# arduinoISP.net
KiCad netlist of a schematic drawn in EAGLE
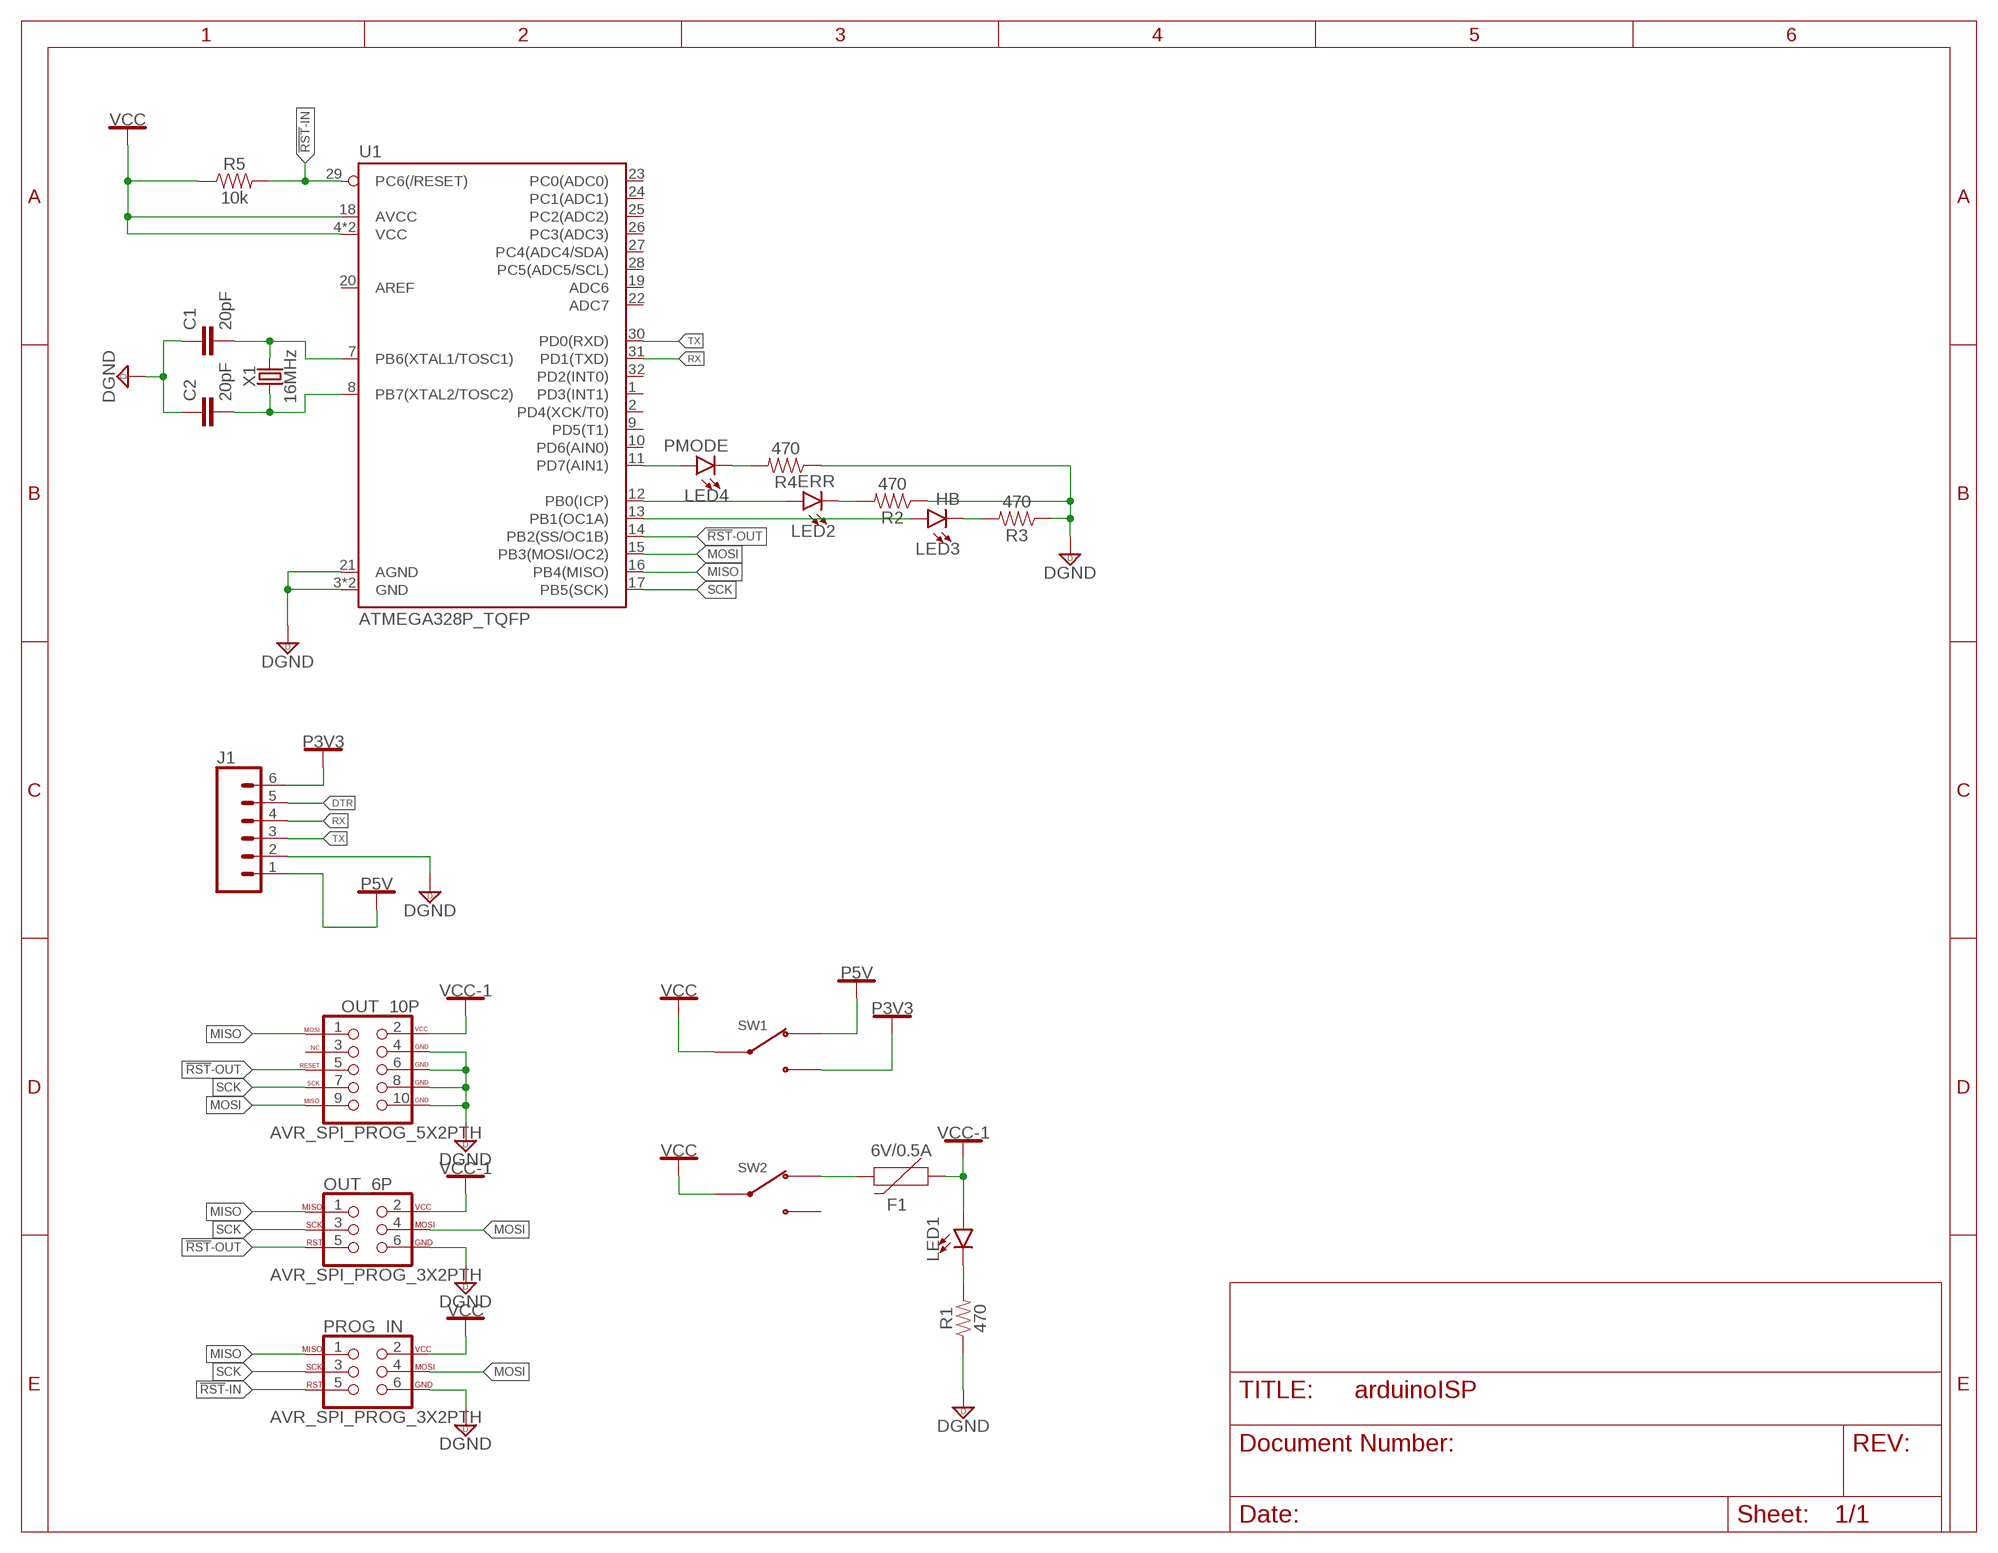
[diagram p0: schematic, sheet 1]

(export (version "E")
  (design (tool "Eeschema 10.0.6"))
  (components
    (comp (ref "C1")
      (value "20pF")
      (footprint "eagle-import:0603")
      (libsource (lib "eagle-import") (part "CAPACITOR_SMT_0603"))
    )
    (comp (ref "C2")
      (value "20pF")
      (footprint "eagle-import:0603")
      (libsource (lib "eagle-import") (part "CAPACITOR_SMT_0603"))
    )
    (comp (ref "F1")
      (value "6V/0.5A")
      (footprint "eagle-import:1206")
      (libsource (lib "eagle-import") (part "PPTC_HALF-AMP"))
    )
    (comp (ref "J1")
      (value "CONN_06NO_SILK_NO_POP")
      (footprint "eagle-import:1X06_NO_SILK")
      (libsource (lib "eagle-import") (part "CONN_06NO_SILK_NO_POP"))
    )
    (comp (ref "LED1")
      (value "LED3MM")
      (footprint "eagle-import:LED_3MM")
      (libsource (lib "eagle-import") (part "LED3MM"))
    )
    (comp (ref "LED2")
      (value "ERR")
      (footprint "eagle-import:LED_3MM")
      (libsource (lib "eagle-import") (part "LED3MM"))
    )
    (comp (ref "LED3")
      (value "HB")
      (footprint "eagle-import:LED_3MM")
      (libsource (lib "eagle-import") (part "LED3MM"))
    )
    (comp (ref "LED4")
      (value "PMODE")
      (footprint "eagle-import:LED_3MM")
      (libsource (lib "eagle-import") (part "LED3MM"))
    )
    (comp (ref "OUT_6P")
      (value "AVR_SPI_PROG_3X2PTH")
      (footprint "eagle-import:2X3")
      (libsource (lib "eagle-import") (part "AVR_SPI_PROG_3X2PTH"))
    )
    (comp (ref "OUT_10P")
      (value "AVR_SPI_PROG_5X2PTH")
      (footprint "eagle-import:2X5")
      (libsource (lib "eagle-import") (part "AVR_SPI_PROG_5X2PTH"))
    )
    (comp (ref "PROG_IN")
      (value "AVR_SPI_PROG_3X2PTH")
      (footprint "eagle-import:2X3")
      (libsource (lib "eagle-import") (part "AVR_SPI_PROG_3X2PTH"))
    )
    (comp (ref "R1")
      (value "470")
      (footprint "eagle-import:0603")
      (libsource (lib "eagle-import") (part "RESISTOR_SMT_0603"))
    )
    (comp (ref "R2")
      (value "470")
      (footprint "eagle-import:0603")
      (libsource (lib "eagle-import") (part "RESISTOR_SMT_0603"))
    )
    (comp (ref "R3")
      (value "470")
      (footprint "eagle-import:0603")
      (libsource (lib "eagle-import") (part "RESISTOR_SMT_0603"))
    )
    (comp (ref "R4")
      (value "470")
      (footprint "eagle-import:0603")
      (libsource (lib "eagle-import") (part "RESISTOR_SMT_0603"))
    )
    (comp (ref "R5")
      (value "10k")
      (footprint "eagle-import:0603")
      (libsource (lib "eagle-import") (part "RESISTOR_SMT_0603"))
    )
    (comp (ref "SW1")
      (value "SW-SPDT_SS-12D02-VG4")
      (footprint "eagle-import:SW_SS-12D10L5_FP")
      (libsource (lib "eagle-import") (part "SW-SPDT_SS-12D02-VG4"))
    )
    (comp (ref "SW2")
      (value "SW-SPDT_SS-12D02-VG4")
      (footprint "eagle-import:SW_SS-12D10L5_FP")
      (libsource (lib "eagle-import") (part "SW-SPDT_SS-12D02-VG4"))
    )
    (comp (ref "U1")
      (value "ATMEGA328P_TQFP")
      (footprint "eagle-import:TQFP32-08")
      (libsource (lib "eagle-import") (part "ATMEGA328P_TQFP"))
    )
    (comp (ref "X1")
      (value "16MHz")
      (footprint "eagle-import:HC49US")
      (libsource (lib "eagle-import") (part "CRYSTAL-16MHZPTH-HC49US"))
    )
  )
  (nets
    (net (code "1") (name "/~{RST}-IN") (class "Default")
      (node (ref "PROG_IN") (pin "5") (pinfunction "5_5") (pintype "passive"))
      (node (ref "R5") (pin "2") (pinfunction "2_2") (pintype "passive"))
      (node (ref "U1") (pin "29") (pinfunction "PC6(/RESET)_29") (pintype "bidirectional"))
    )
    (net (code "2") (name "/~{RST}-OUT") (class "Default")
      (node (ref "OUT_10P") (pin "5") (pinfunction "RESET_5") (pintype "passive"))
      (node (ref "OUT_6P") (pin "5") (pinfunction "5_5") (pintype "passive"))
      (node (ref "U1") (pin "14") (pinfunction "PB2(SS/OC1B)_14") (pintype "bidirectional"))
    )
    (net (code "3") (name "DGND") (class "Default")
      (node (ref "C1") (pin "1") (pinfunction "1_1") (pintype "passive"))
      (node (ref "C2") (pin "1") (pinfunction "1_1") (pintype "passive"))
      (node (ref "J1") (pin "2") (pinfunction "2_2") (pintype "passive"))
      (node (ref "OUT_10P") (pin "10") (pinfunction "GND_10") (pintype "power_in"))
      (node (ref "OUT_10P") (pin "4") (pinfunction "GND_4") (pintype "power_in"))
      (node (ref "OUT_10P") (pin "6") (pinfunction "GND_6") (pintype "power_in"))
      (node (ref "OUT_10P") (pin "8") (pinfunction "GND_8") (pintype "power_in"))
      (node (ref "OUT_6P") (pin "6") (pinfunction "6_6") (pintype "passive"))
      (node (ref "PROG_IN") (pin "6") (pinfunction "6_6") (pintype "passive"))
      (node (ref "R1") (pin "1") (pinfunction "1_1") (pintype "passive"))
      (node (ref "R2") (pin "1") (pinfunction "1_1") (pintype "passive"))
      (node (ref "R3") (pin "1") (pinfunction "1_1") (pintype "passive"))
      (node (ref "R4") (pin "1") (pinfunction "1_1") (pintype "passive"))
      (node (ref "U1") (pin "21") (pinfunction "AGND_21") (pintype "bidirectional"))
      (node (ref "U1") (pin "3") (pinfunction "GND_3") (pintype "bidirectional"))
      (node (ref "U1") (pin "5") (pinfunction "GND_5") (pintype "bidirectional"))
    )
    (net (code "4") (name "DTR") (class "Default")
      (node (ref "J1") (pin "5") (pinfunction "5_5") (pintype "passive"))
    )
    (net (code "5") (name "MISO") (class "Default")
      (node (ref "OUT_10P") (pin "1") (pinfunction "MOSI_1") (pintype "passive"))
      (node (ref "OUT_6P") (pin "1") (pinfunction "1_1") (pintype "passive"))
      (node (ref "PROG_IN") (pin "1") (pinfunction "1_1") (pintype "passive"))
      (node (ref "U1") (pin "16") (pinfunction "PB4(MISO)_16") (pintype "bidirectional"))
    )
    (net (code "6") (name "MOSI") (class "Default")
      (node (ref "OUT_10P") (pin "9") (pinfunction "MISO_9") (pintype "passive"))
      (node (ref "OUT_6P") (pin "4") (pinfunction "4_4") (pintype "passive"))
      (node (ref "PROG_IN") (pin "4") (pinfunction "4_4") (pintype "passive"))
      (node (ref "U1") (pin "15") (pinfunction "PB3(MOSI/OC2)_15") (pintype "bidirectional"))
    )
    (net (code "7") (name "Net-(LED1-C)") (class "Default")
      (node (ref "LED1") (pin "K") (pinfunction "C_K") (pintype "passive"))
      (node (ref "R1") (pin "2") (pinfunction "2_2") (pintype "passive"))
    )
    (net (code "8") (name "Net-(LED2-C)") (class "Default")
      (node (ref "LED2") (pin "K") (pinfunction "C_K") (pintype "passive"))
      (node (ref "R2") (pin "2") (pinfunction "2_2") (pintype "passive"))
    )
    (net (code "9") (name "Net-(LED3-C)") (class "Default")
      (node (ref "LED3") (pin "K") (pinfunction "C_K") (pintype "passive"))
      (node (ref "R3") (pin "2") (pinfunction "2_2") (pintype "passive"))
    )
    (net (code "10") (name "Net-(LED4-C)") (class "Default")
      (node (ref "LED4") (pin "K") (pinfunction "C_K") (pintype "passive"))
      (node (ref "R4") (pin "2") (pinfunction "2_2") (pintype "passive"))
    )
    (net (code "11") (name "Net-(SW2-A)") (class "Default")
      (node (ref "F1") (pin "2") (pinfunction "2_2") (pintype "bidirectional"))
      (node (ref "SW2") (pin "P$1") (pinfunction "A_P$1") (pintype "bidirectional"))
    )
    (net (code "12") (name "Net-(U1-PB0(ICP))") (class "Default")
      (node (ref "LED2") (pin "A") (pinfunction "A_A") (pintype "passive"))
      (node (ref "U1") (pin "12") (pinfunction "PB0(ICP)_12") (pintype "bidirectional"))
    )
    (net (code "13") (name "Net-(U1-PB1(OC1A))") (class "Default")
      (node (ref "LED3") (pin "A") (pinfunction "A_A") (pintype "passive"))
      (node (ref "U1") (pin "13") (pinfunction "PB1(OC1A)_13") (pintype "bidirectional"))
    )
    (net (code "14") (name "Net-(U1-PB6(XTAL1{slash}TOSC1))") (class "Default")
      (node (ref "C1") (pin "2") (pinfunction "2_2") (pintype "passive"))
      (node (ref "U1") (pin "7") (pinfunction "PB6(XTAL1/TOSC1)_7") (pintype "bidirectional"))
      (node (ref "X1") (pin "2") (pinfunction "2_2") (pintype "passive"))
    )
    (net (code "15") (name "Net-(U1-PB7(XTAL2{slash}TOSC2))") (class "Default")
      (node (ref "C2") (pin "2") (pinfunction "2_2") (pintype "passive"))
      (node (ref "U1") (pin "8") (pinfunction "PB7(XTAL2/TOSC2)_8") (pintype "bidirectional"))
      (node (ref "X1") (pin "1") (pinfunction "1_1") (pintype "passive"))
    )
    (net (code "16") (name "Net-(U1-PD7(AIN1))") (class "Default")
      (node (ref "LED4") (pin "A") (pinfunction "A_A") (pintype "passive"))
      (node (ref "U1") (pin "11") (pinfunction "PD7(AIN1)_11") (pintype "bidirectional"))
    )
    (net (code "17") (name "P3V3") (class "Default")
      (node (ref "J1") (pin "6") (pinfunction "6_6") (pintype "passive"))
      (node (ref "SW1") (pin "P$3") (pinfunction "B_P$3") (pintype "bidirectional"))
    )
    (net (code "18") (name "P5V") (class "Default")
      (node (ref "J1") (pin "1") (pinfunction "1_1") (pintype "passive"))
      (node (ref "SW1") (pin "P$1") (pinfunction "A_P$1") (pintype "bidirectional"))
    )
    (net (code "19") (name "RX") (class "Default")
      (node (ref "J1") (pin "4") (pinfunction "4_4") (pintype "passive"))
      (node (ref "U1") (pin "31") (pinfunction "PD1(TXD)_31") (pintype "bidirectional"))
    )
    (net (code "20") (name "SCK") (class "Default")
      (node (ref "OUT_10P") (pin "7") (pinfunction "SCK_7") (pintype "passive"))
      (node (ref "OUT_6P") (pin "3") (pinfunction "3_3") (pintype "passive"))
      (node (ref "PROG_IN") (pin "3") (pinfunction "3_3") (pintype "passive"))
      (node (ref "U1") (pin "17") (pinfunction "PB5(SCK)_17") (pintype "bidirectional"))
    )
    (net (code "21") (name "TX") (class "Default")
      (node (ref "J1") (pin "3") (pinfunction "3_3") (pintype "passive"))
      (node (ref "U1") (pin "30") (pinfunction "PD0(RXD)_30") (pintype "bidirectional"))
    )
    (net (code "22") (name "VCC") (class "Default")
      (node (ref "PROG_IN") (pin "2") (pinfunction "2_2") (pintype "passive"))
      (node (ref "R5") (pin "1") (pinfunction "1_1") (pintype "passive"))
      (node (ref "SW1") (pin "P$2") (pinfunction "COM_P$2") (pintype "bidirectional"))
      (node (ref "SW2") (pin "P$2") (pinfunction "COM_P$2") (pintype "bidirectional"))
      (node (ref "U1") (pin "18") (pinfunction "AVCC_18") (pintype "bidirectional"))
      (node (ref "U1") (pin "4") (pinfunction "VCC_4") (pintype "bidirectional"))
      (node (ref "U1") (pin "6") (pinfunction "VCC_6") (pintype "bidirectional"))
    )
    (net (code "23") (name "VCC-1") (class "Default")
      (node (ref "F1") (pin "1") (pinfunction "1_1") (pintype "bidirectional"))
      (node (ref "LED1") (pin "A") (pinfunction "A_A") (pintype "passive"))
      (node (ref "OUT_10P") (pin "2") (pinfunction "VCC_2") (pintype "power_in"))
      (node (ref "OUT_6P") (pin "2") (pinfunction "2_2") (pintype "passive"))
    )
    (net (code "24") (name "unconnected-(OUT_10P-NC-Pad3)") (class "Default")
      (node (ref "OUT_10P") (pin "3") (pinfunction "NC_3") (pintype "no_connect"))
    )
    (net (code "25") (name "unconnected-(SW2-B-PadP$3)") (class "Default")
      (node (ref "SW2") (pin "P$3") (pinfunction "B_P$3") (pintype "bidirectional"))
    )
    (net (code "26") (name "unconnected-(U1-ADC6-Pad19)") (class "Default")
      (node (ref "U1") (pin "19") (pinfunction "ADC6_19") (pintype "bidirectional"))
    )
    (net (code "27") (name "unconnected-(U1-ADC7-Pad22)") (class "Default")
      (node (ref "U1") (pin "22") (pinfunction "ADC7_22") (pintype "bidirectional"))
    )
    (net (code "28") (name "unconnected-(U1-AREF-Pad20)") (class "Default")
      (node (ref "U1") (pin "20") (pinfunction "AREF_20") (pintype "bidirectional"))
    )
    (net (code "29") (name "unconnected-(U1-PC0(ADC0)-Pad23)") (class "Default")
      (node (ref "U1") (pin "23") (pinfunction "PC0(ADC0)_23") (pintype "bidirectional"))
    )
    (net (code "30") (name "unconnected-(U1-PC1(ADC1)-Pad24)") (class "Default")
      (node (ref "U1") (pin "24") (pinfunction "PC1(ADC1)_24") (pintype "bidirectional"))
    )
    (net (code "31") (name "unconnected-(U1-PC2(ADC2)-Pad25)") (class "Default")
      (node (ref "U1") (pin "25") (pinfunction "PC2(ADC2)_25") (pintype "bidirectional"))
    )
    (net (code "32") (name "unconnected-(U1-PC3(ADC3)-Pad26)") (class "Default")
      (node (ref "U1") (pin "26") (pinfunction "PC3(ADC3)_26") (pintype "bidirectional"))
    )
    (net (code "33") (name "unconnected-(U1-PC4(ADC4{slash}SDA)-Pad27)") (class "Default")
      (node (ref "U1") (pin "27") (pinfunction "PC4(ADC4/SDA)_27") (pintype "bidirectional"))
    )
    (net (code "34") (name "unconnected-(U1-PC5(ADC5{slash}SCL)-Pad28)") (class "Default")
      (node (ref "U1") (pin "28") (pinfunction "PC5(ADC5/SCL)_28") (pintype "bidirectional"))
    )
    (net (code "35") (name "unconnected-(U1-PD2(INT0)-Pad32)") (class "Default")
      (node (ref "U1") (pin "32") (pinfunction "PD2(INT0)_32") (pintype "bidirectional"))
    )
    (net (code "36") (name "unconnected-(U1-PD3(INT1)-Pad1)") (class "Default")
      (node (ref "U1") (pin "1") (pinfunction "PD3(INT1)_1") (pintype "bidirectional"))
    )
    (net (code "37") (name "unconnected-(U1-PD4(XCK{slash}T0)-Pad2)") (class "Default")
      (node (ref "U1") (pin "2") (pinfunction "PD4(XCK/T0)_2") (pintype "bidirectional"))
    )
    (net (code "38") (name "unconnected-(U1-PD5(T1)-Pad9)") (class "Default")
      (node (ref "U1") (pin "9") (pinfunction "PD5(T1)_9") (pintype "bidirectional"))
    )
    (net (code "39") (name "unconnected-(U1-PD6(AIN0)-Pad10)") (class "Default")
      (node (ref "U1") (pin "10") (pinfunction "PD6(AIN0)_10") (pintype "bidirectional"))
    )
  )
)
